# USER_IO.net
KiCad netlist of a schematic drawn in Altium Designer
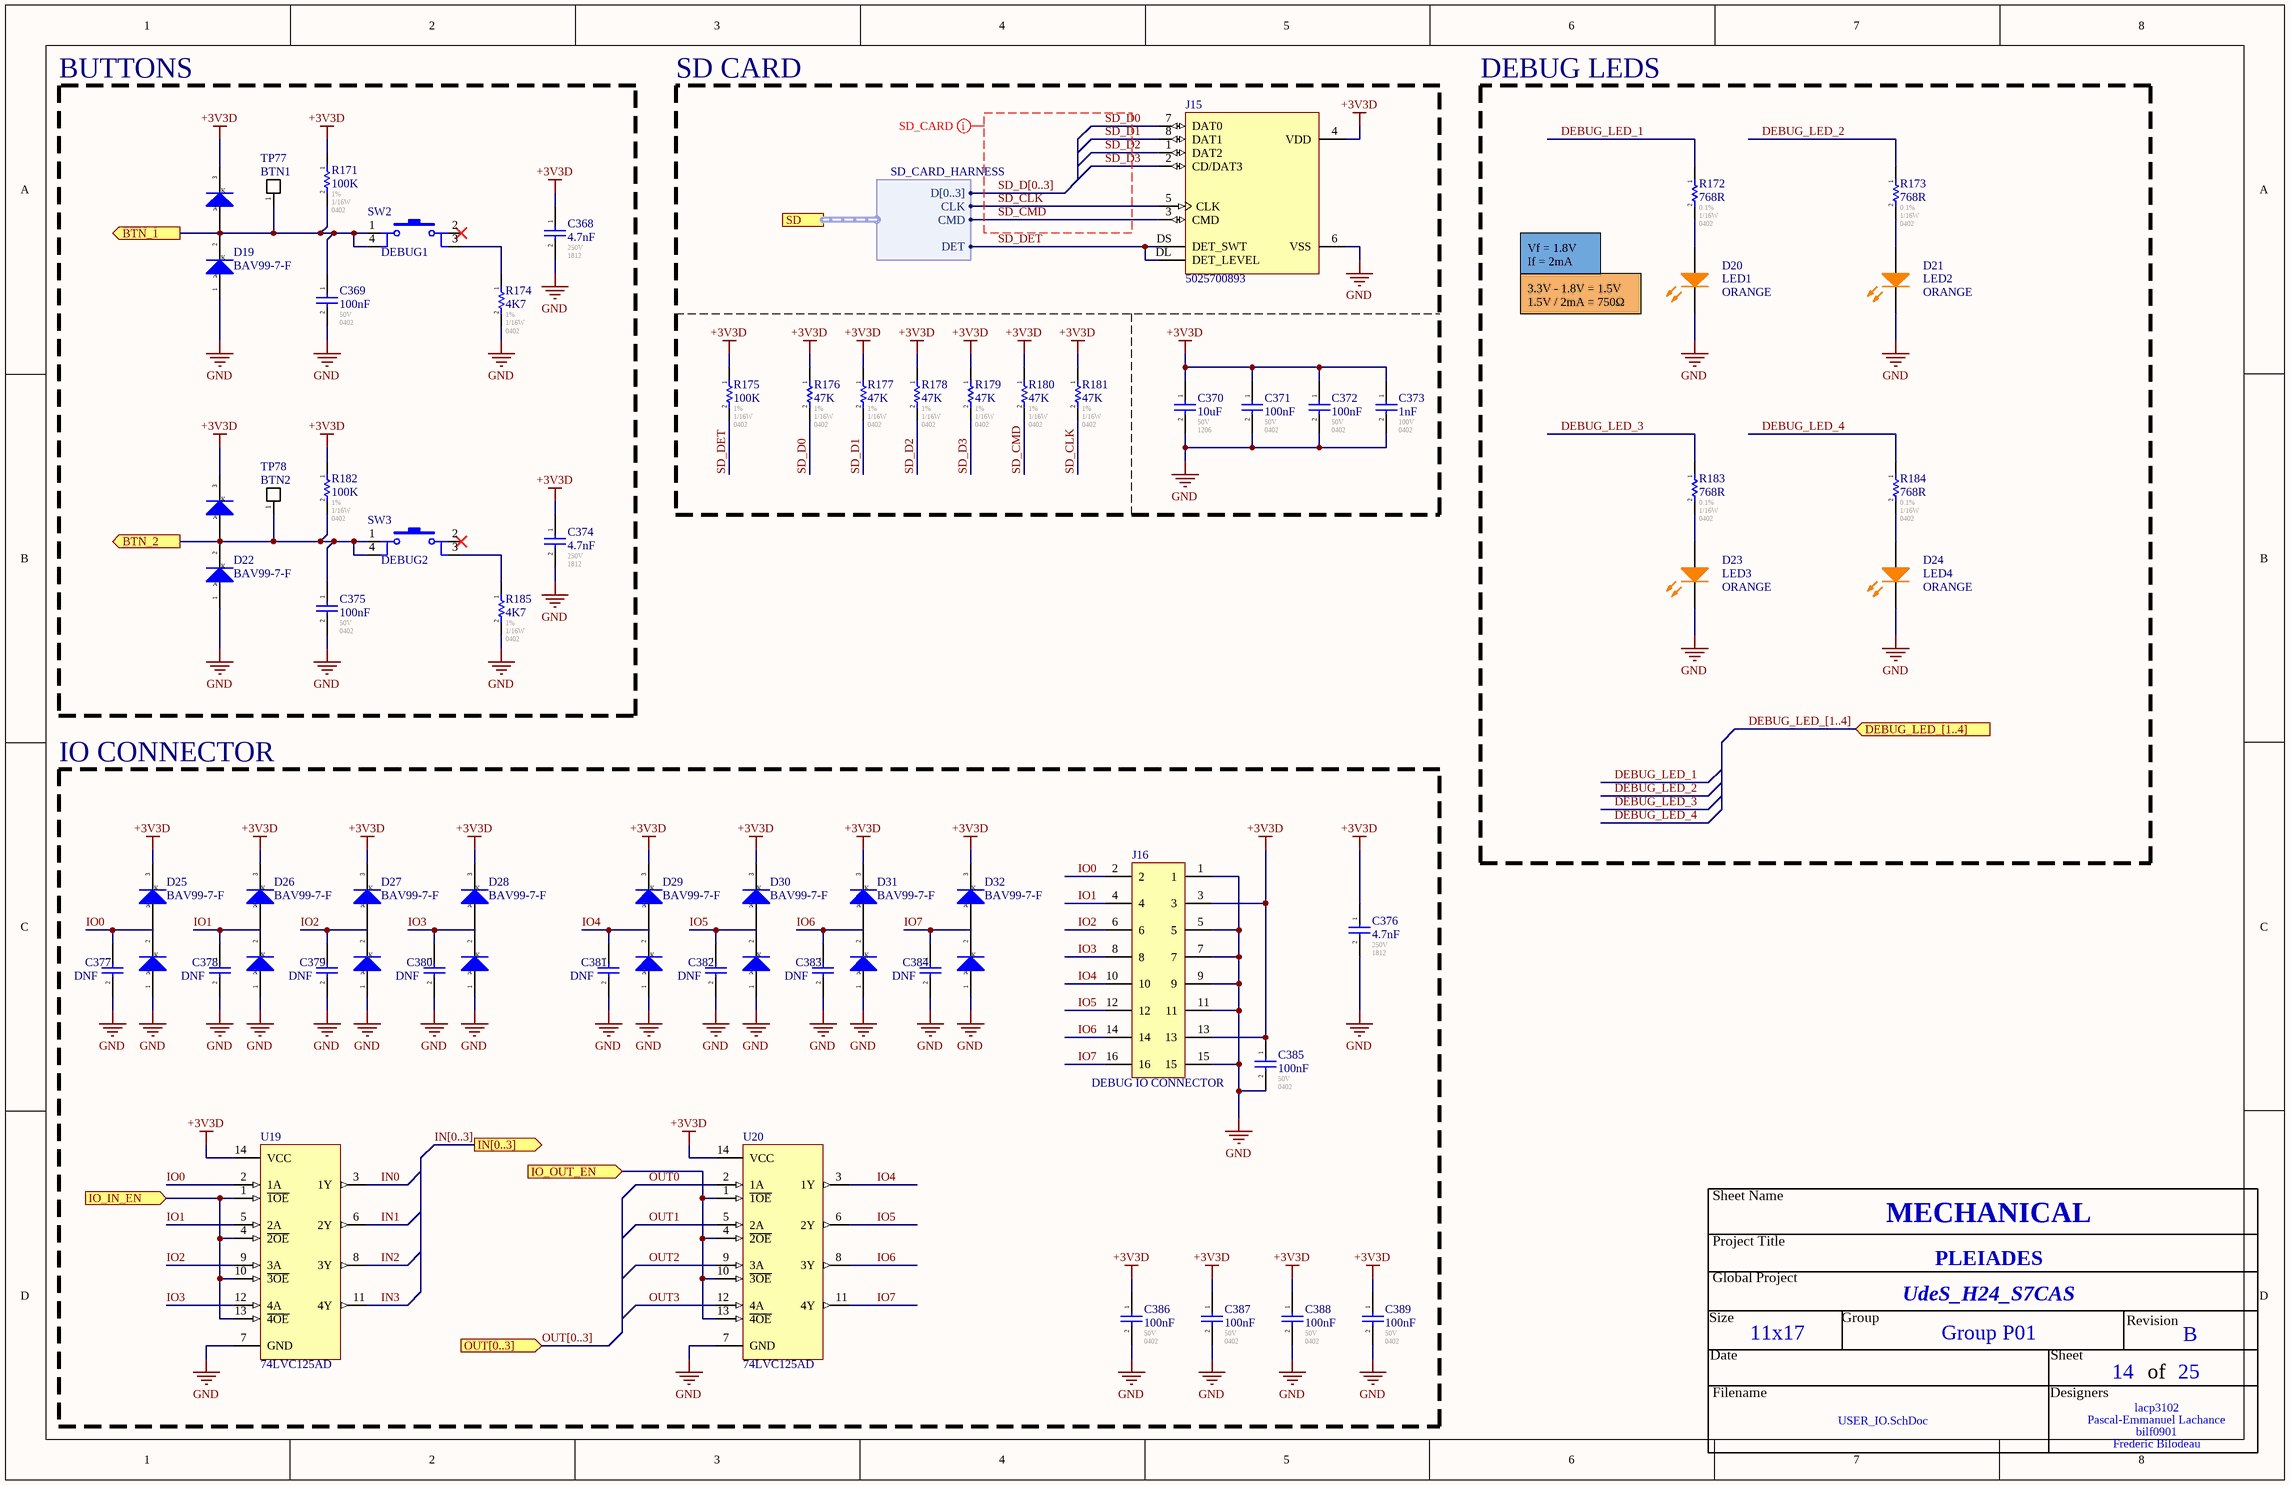
[diagram p0: USER_IO.SchDoc]

(export (version "E")
  (design (tool "Eeschema 10.0.6"))
  (components
    (comp (ref "C368")
      (value "4.7nF")
      (footprint "1812")
      (description "GA343DR7GD472KW01L\r\n0402 4.7nF 10% X7R 1812 250VAC Ceramic Capacitor")
      (fields
        (field (name "MFR") "Murata")
        (field (name "VOLTAGE - RATED") "250V")
        (field (name "TOLERANCE") "10%")
      )
      (libsource (lib "Symbols") (part "CAP_CER"))
    )
    (comp (ref "C369")
      (value "100nF")
      (footprint "0402")
      (description "GCM155R71H104KE02J\r\n0402 100nF 10% X7R Ceramic Capacitor")
      (fields
        (field (name "MFR") "Murata")
        (field (name "PART#") "GCM155R71H104KE02J")
        (field (name "VOLTAGE - RATED") "50V")
      )
      (libsource (lib "Symbols") (part "CAP_CER"))
    )
    (comp (ref "C370")
      (value "10uF")
      (footprint "1206")
      (description "GRT31CR61H106KE01L\r\n1206 10uF 10% X5R Ceramic Capacitor")
      (fields
        (field (name "MFR") "Murata")
        (field (name "VOLTAGE - RATED") "50V")
        (field (name "TOLERANCE") "10%")
      )
      (libsource (lib "Symbols") (part "CAP_CER"))
    )
    (comp (ref "C371")
      (value "100nF")
      (footprint "0402")
      (description "GCM155R71H104KE02J\r\n0402 100nF 10% X7R Ceramic Capacitor")
      (fields
        (field (name "MFR") "Murata")
        (field (name "PART#") "GCM155R71H104KE02J")
        (field (name "VOLTAGE - RATED") "50V")
      )
      (libsource (lib "Symbols") (part "CAP_CER"))
    )
    (comp (ref "C372")
      (value "100nF")
      (footprint "0402")
      (description "GCM155R71H104KE02J\r\n0402 100nF 10% X7R Ceramic Capacitor")
      (fields
        (field (name "MFR") "Murata")
        (field (name "PART#") "GCM155R71H104KE02J")
        (field (name "VOLTAGE - RATED") "50V")
      )
      (libsource (lib "Symbols") (part "CAP_CER"))
    )
    (comp (ref "C373")
      (value "1nF")
      (footprint "0402")
      (description "GCM155R72A102KA37D\r\n0402 1nF 10% X7R Ceramic Capacitor")
      (fields
        (field (name "MFR") "Murata")
        (field (name "PART#") "GCM155R72A102KA37D")
        (field (name "VOLTAGE - RATED") "100V")
      )
      (libsource (lib "Symbols") (part "CAP_CER"))
    )
    (comp (ref "C374")
      (value "4.7nF")
      (footprint "1812")
      (description "GA343DR7GD472KW01L\r\n0402 4.7nF 10% X7R 1812 250VAC Ceramic Capacitor")
      (fields
        (field (name "MFR") "Murata")
        (field (name "VOLTAGE - RATED") "250V")
        (field (name "TOLERANCE") "10%")
      )
      (libsource (lib "Symbols") (part "CAP_CER"))
    )
    (comp (ref "C375")
      (value "100nF")
      (footprint "0402")
      (description "GCM155R71H104KE02J\r\n0402 100nF 10% X7R Ceramic Capacitor")
      (fields
        (field (name "MFR") "Murata")
        (field (name "PART#") "GCM155R71H104KE02J")
        (field (name "VOLTAGE - RATED") "50V")
      )
      (libsource (lib "Symbols") (part "CAP_CER"))
    )
    (comp (ref "C376")
      (value "4.7nF")
      (footprint "1812")
      (description "GA343DR7GD472KW01L\r\n0402 4.7nF 10% X7R 1812 250VAC Ceramic Capacitor")
      (fields
        (field (name "MFR") "Murata")
        (field (name "VOLTAGE - RATED") "250V")
        (field (name "TOLERANCE") "10%")
      )
      (libsource (lib "Symbols") (part "CAP_CER"))
    )
    (comp (ref "C377") (value "DNF") (footprint "CAP_0402") (libsource (lib "Symbols") (part "CAP_CER")))
    (comp (ref "C378") (value "DNF") (footprint "CAP_0402") (libsource (lib "Symbols") (part "CAP_CER")))
    (comp (ref "C379") (value "DNF") (footprint "CAP_0402") (libsource (lib "Symbols") (part "CAP_CER")))
    (comp (ref "C380") (value "DNF") (footprint "CAP_0402") (libsource (lib "Symbols") (part "CAP_CER")))
    (comp (ref "C381") (value "DNF") (footprint "CAP_0402") (libsource (lib "Symbols") (part "CAP_CER")))
    (comp (ref "C382") (value "DNF") (footprint "CAP_0402") (libsource (lib "Symbols") (part "CAP_CER")))
    (comp (ref "C383") (value "DNF") (footprint "CAP_0402") (libsource (lib "Symbols") (part "CAP_CER")))
    (comp (ref "C384") (value "DNF") (footprint "CAP_0402") (libsource (lib "Symbols") (part "CAP_CER")))
    (comp (ref "C385")
      (value "100nF")
      (footprint "0402")
      (description "GCM155R71H104KE02J\r\n0402 100nF 10% X7R Ceramic Capacitor")
      (fields
        (field (name "MFR") "Murata")
        (field (name "PART#") "GCM155R71H104KE02J")
        (field (name "VOLTAGE - RATED") "50V")
      )
      (libsource (lib "Symbols") (part "CAP_CER"))
    )
    (comp (ref "C386")
      (value "100nF")
      (footprint "0402")
      (description "GCM155R71H104KE02J\r\n0402 100nF 10% X7R Ceramic Capacitor")
      (fields
        (field (name "MFR") "Murata")
        (field (name "PART#") "GCM155R71H104KE02J")
        (field (name "VOLTAGE - RATED") "50V")
      )
      (libsource (lib "Symbols") (part "CAP_CER"))
    )
    (comp (ref "C387")
      (value "100nF")
      (footprint "0402")
      (description "GCM155R71H104KE02J\r\n0402 100nF 10% X7R Ceramic Capacitor")
      (fields
        (field (name "MFR") "Murata")
        (field (name "PART#") "GCM155R71H104KE02J")
        (field (name "VOLTAGE - RATED") "50V")
      )
      (libsource (lib "Symbols") (part "CAP_CER"))
    )
    (comp (ref "C388")
      (value "100nF")
      (footprint "0402")
      (description "GCM155R71H104KE02J\r\n0402 100nF 10% X7R Ceramic Capacitor")
      (fields
        (field (name "MFR") "Murata")
        (field (name "PART#") "GCM155R71H104KE02J")
        (field (name "VOLTAGE - RATED") "50V")
      )
      (libsource (lib "Symbols") (part "CAP_CER"))
    )
    (comp (ref "C389")
      (value "100nF")
      (footprint "0402")
      (description "GCM155R71H104KE02J\r\n0402 100nF 10% X7R Ceramic Capacitor")
      (fields
        (field (name "MFR") "Murata")
        (field (name "PART#") "GCM155R71H104KE02J")
        (field (name "VOLTAGE - RATED") "50V")
      )
      (libsource (lib "Symbols") (part "CAP_CER"))
    )
    (comp (ref "D19")
      (value "BAV99-7-F")
      (footprint "SOT23-3")
      (description "Diode Array 1 Pair Series Connection 75 V 300mA (DC) Surface Mount TO-236-3, SC-59, SOT-23-3")
      (fields (field (name "MFR") "Diodes Incorporated"))
      (libsource (lib "Symbols") (part "DIODE_TVS_DUAL"))
    )
    (comp (ref "D20")
      (value "LED1")
      (footprint "LED_0603")
      (description "LED - 611nM ORANGE 2mA - 0603")
      (fields
        (field (name "VOLTAGE") "1.8V")
        (field (name "MFG") "ROHM Semiconductor")
        (field (name "ALTIUM_VALUE") "ORANGE")
        (field (name "CREATEDBY") "Jonathan Bouchard")
      )
      (libsource (lib "S7CAS_LIB2023") (part "LED_SML-311DTT86"))
    )
    (comp (ref "D21")
      (value "LED2")
      (footprint "LED_0603")
      (description "LED - 611nM ORANGE 2mA - 0603")
      (fields
        (field (name "VOLTAGE") "1.8V")
        (field (name "MFG") "ROHM Semiconductor")
        (field (name "ALTIUM_VALUE") "ORANGE")
        (field (name "CREATEDBY") "Jonathan Bouchard")
      )
      (libsource (lib "S7CAS_LIB2023") (part "LED_SML-311DTT86"))
    )
    (comp (ref "D22")
      (value "BAV99-7-F")
      (footprint "SOT23-3")
      (description "Diode Array 1 Pair Series Connection 75 V 300mA (DC) Surface Mount TO-236-3, SC-59, SOT-23-3")
      (fields (field (name "MFR") "Diodes Incorporated"))
      (libsource (lib "Symbols") (part "DIODE_TVS_DUAL"))
    )
    (comp (ref "D23")
      (value "LED3")
      (footprint "LED_0603")
      (description "LED - 611nM ORANGE 2mA - 0603")
      (fields
        (field (name "VOLTAGE") "1.8V")
        (field (name "MFG") "ROHM Semiconductor")
        (field (name "ALTIUM_VALUE") "ORANGE")
        (field (name "CREATEDBY") "Jonathan Bouchard")
      )
      (libsource (lib "S7CAS_LIB2023") (part "LED_SML-311DTT86"))
    )
    (comp (ref "D24")
      (value "LED4")
      (footprint "LED_0603")
      (description "LED - 611nM ORANGE 2mA - 0603")
      (fields
        (field (name "VOLTAGE") "1.8V")
        (field (name "MFG") "ROHM Semiconductor")
        (field (name "ALTIUM_VALUE") "ORANGE")
        (field (name "CREATEDBY") "Jonathan Bouchard")
      )
      (libsource (lib "S7CAS_LIB2023") (part "LED_SML-311DTT86"))
    )
    (comp (ref "D25")
      (value "BAV99-7-F")
      (footprint "SOT23-3")
      (description "Diode Array 1 Pair Series Connection 75 V 300mA (DC) Surface Mount TO-236-3, SC-59, SOT-23-3")
      (fields (field (name "MFR") "Diodes Incorporated"))
      (libsource (lib "Symbols") (part "DIODE_TVS_DUAL"))
    )
    (comp (ref "D26")
      (value "BAV99-7-F")
      (footprint "SOT23-3")
      (description "Diode Array 1 Pair Series Connection 75 V 300mA (DC) Surface Mount TO-236-3, SC-59, SOT-23-3")
      (fields (field (name "MFR") "Diodes Incorporated"))
      (libsource (lib "Symbols") (part "DIODE_TVS_DUAL"))
    )
    (comp (ref "D27")
      (value "BAV99-7-F")
      (footprint "SOT23-3")
      (description "Diode Array 1 Pair Series Connection 75 V 300mA (DC) Surface Mount TO-236-3, SC-59, SOT-23-3")
      (fields (field (name "MFR") "Diodes Incorporated"))
      (libsource (lib "Symbols") (part "DIODE_TVS_DUAL"))
    )
    (comp (ref "D28")
      (value "BAV99-7-F")
      (footprint "SOT23-3")
      (description "Diode Array 1 Pair Series Connection 75 V 300mA (DC) Surface Mount TO-236-3, SC-59, SOT-23-3")
      (fields (field (name "MFR") "Diodes Incorporated"))
      (libsource (lib "Symbols") (part "DIODE_TVS_DUAL"))
    )
    (comp (ref "D29")
      (value "BAV99-7-F")
      (footprint "SOT23-3")
      (description "Diode Array 1 Pair Series Connection 75 V 300mA (DC) Surface Mount TO-236-3, SC-59, SOT-23-3")
      (fields (field (name "MFR") "Diodes Incorporated"))
      (libsource (lib "Symbols") (part "DIODE_TVS_DUAL"))
    )
    (comp (ref "D30")
      (value "BAV99-7-F")
      (footprint "SOT23-3")
      (description "Diode Array 1 Pair Series Connection 75 V 300mA (DC) Surface Mount TO-236-3, SC-59, SOT-23-3")
      (fields (field (name "MFR") "Diodes Incorporated"))
      (libsource (lib "Symbols") (part "DIODE_TVS_DUAL"))
    )
    (comp (ref "D31")
      (value "BAV99-7-F")
      (footprint "SOT23-3")
      (description "Diode Array 1 Pair Series Connection 75 V 300mA (DC) Surface Mount TO-236-3, SC-59, SOT-23-3")
      (fields (field (name "MFR") "Diodes Incorporated"))
      (libsource (lib "Symbols") (part "DIODE_TVS_DUAL"))
    )
    (comp (ref "D32")
      (value "BAV99-7-F")
      (footprint "SOT23-3")
      (description "Diode Array 1 Pair Series Connection 75 V 300mA (DC) Surface Mount TO-236-3, SC-59, SOT-23-3")
      (fields (field (name "MFR") "Diodes Incorporated"))
      (libsource (lib "Symbols") (part "DIODE_TVS_DUAL"))
    )
    (comp (ref "J15")
      (value "5025700893")
      (footprint "MICROSD_5025700893")
      (description "10 (8 + 2) Position Card Connector Secure Digital - microSD™ Surface Mount, Right Angle Gold")
      (libsource (lib "Connectors") (part "MICROSD_10"))
    )
    (comp (ref "J16")
      (value "DEBUG IO CONNECTOR")
      (footprint "HEADER-16_100MIL")
      (libsource (lib "Connectors") (part "HEADER_16"))
    )
    (comp (ref "R171")
      (value "100K")
      (footprint "RES_0402")
      (fields
        (field (name "TOLERANCE") "1%")
        (field (name "POWER") "1/16W")
        (field (name "PACKAGE / CASE") "0402")
      )
      (libsource (lib "Symbols") (part "RESISTOR"))
    )
    (comp (ref "R172")
      (value "768R")
      (footprint "RES_0402")
      (fields
        (field (name "TOLERANCE") "0.1%")
        (field (name "POWER") "1/16W")
        (field (name "PACKAGE / CASE") "0402")
      )
      (libsource (lib "Symbols") (part "RESISTOR"))
    )
    (comp (ref "R173")
      (value "768R")
      (footprint "RES_0402")
      (fields
        (field (name "TOLERANCE") "0.1%")
        (field (name "POWER") "1/16W")
        (field (name "PACKAGE / CASE") "0402")
      )
      (libsource (lib "Symbols") (part "RESISTOR"))
    )
    (comp (ref "R174")
      (value "4K7")
      (footprint "RES_0402")
      (fields
        (field (name "TOLERANCE") "1%")
        (field (name "POWER") "1/16W")
        (field (name "PACKAGE / CASE") "0402")
      )
      (libsource (lib "Symbols") (part "RESISTOR"))
    )
    (comp (ref "R175")
      (value "100K")
      (footprint "RES_0402")
      (fields
        (field (name "TOLERANCE") "1%")
        (field (name "POWER") "1/16W")
        (field (name "PACKAGE / CASE") "0402")
      )
      (libsource (lib "Symbols") (part "RESISTOR"))
    )
    (comp (ref "R176")
      (value "47K")
      (footprint "RES_0402")
      (fields
        (field (name "TOLERANCE") "1%")
        (field (name "POWER") "1/16W")
        (field (name "PACKAGE / CASE") "0402")
      )
      (libsource (lib "Symbols") (part "RESISTOR"))
    )
    (comp (ref "R177")
      (value "47K")
      (footprint "RES_0402")
      (fields
        (field (name "TOLERANCE") "1%")
        (field (name "POWER") "1/16W")
        (field (name "PACKAGE / CASE") "0402")
      )
      (libsource (lib "Symbols") (part "RESISTOR"))
    )
    (comp (ref "R178")
      (value "47K")
      (footprint "RES_0402")
      (fields
        (field (name "TOLERANCE") "1%")
        (field (name "POWER") "1/16W")
        (field (name "PACKAGE / CASE") "0402")
      )
      (libsource (lib "Symbols") (part "RESISTOR"))
    )
    (comp (ref "R179")
      (value "47K")
      (footprint "RES_0402")
      (fields
        (field (name "TOLERANCE") "1%")
        (field (name "POWER") "1/16W")
        (field (name "PACKAGE / CASE") "0402")
      )
      (libsource (lib "Symbols") (part "RESISTOR"))
    )
    (comp (ref "R180")
      (value "47K")
      (footprint "RES_0402")
      (fields
        (field (name "TOLERANCE") "1%")
        (field (name "POWER") "1/16W")
        (field (name "PACKAGE / CASE") "0402")
      )
      (libsource (lib "Symbols") (part "RESISTOR"))
    )
    (comp (ref "R181")
      (value "47K")
      (footprint "RES_0402")
      (fields
        (field (name "TOLERANCE") "1%")
        (field (name "POWER") "1/16W")
        (field (name "PACKAGE / CASE") "0402")
      )
      (libsource (lib "Symbols") (part "RESISTOR"))
    )
    (comp (ref "R182")
      (value "100K")
      (footprint "RES_0402")
      (fields
        (field (name "TOLERANCE") "1%")
        (field (name "POWER") "1/16W")
        (field (name "PACKAGE / CASE") "0402")
      )
      (libsource (lib "Symbols") (part "RESISTOR"))
    )
    (comp (ref "R183")
      (value "768R")
      (footprint "RES_0402")
      (fields
        (field (name "TOLERANCE") "0.1%")
        (field (name "POWER") "1/16W")
        (field (name "PACKAGE / CASE") "0402")
      )
      (libsource (lib "Symbols") (part "RESISTOR"))
    )
    (comp (ref "R184")
      (value "768R")
      (footprint "RES_0402")
      (fields
        (field (name "TOLERANCE") "0.1%")
        (field (name "POWER") "1/16W")
        (field (name "PACKAGE / CASE") "0402")
      )
      (libsource (lib "Symbols") (part "RESISTOR"))
    )
    (comp (ref "R185")
      (value "4K7")
      (footprint "RES_0402")
      (fields
        (field (name "TOLERANCE") "1%")
        (field (name "POWER") "1/16W")
        (field (name "PACKAGE / CASE") "0402")
      )
      (libsource (lib "Symbols") (part "RESISTOR"))
    )
    (comp (ref "SW2")
      (value "DEBUG1")
      (footprint "SWI_TACT_B3SN-3012P")
      (description "SWI - TACT SPST-NO 0.05A 24V - 4-SMD")
      (fields
        (field (name "MFG") "Omron")
        (field (name "MFG PART NUMBER") "B3SN-3012P")
        (field (name "CREATEDBY") "Jonathan Bouchard")
      )
      (libsource (lib "S7CAS_LIB2023") (part "SWI_TACT_B3SN-3012P"))
    )
    (comp (ref "SW3")
      (value "DEBUG2")
      (footprint "SWI_TACT_B3SN-3012P")
      (description "SWI - TACT SPST-NO 0.05A 24V - 4-SMD")
      (fields
        (field (name "MFG") "Omron")
        (field (name "MFG PART NUMBER") "B3SN-3012P")
        (field (name "CREATEDBY") "Jonathan Bouchard")
      )
      (libsource (lib "S7CAS_LIB2023") (part "SWI_TACT_B3SN-3012P"))
    )
    (comp (ref "TP77")
      (value "BTN1")
      (footprint "TP_PAD")
      (description "Test Point")
      (libsource (lib "Symbols") (part "TESTPOINT_PAD"))
    )
    (comp (ref "TP78")
      (value "BTN2")
      (footprint "TP_PAD")
      (description "Test Point")
      (libsource (lib "Symbols") (part "TESTPOINT_PAD"))
    )
    (comp (ref "U19")
      (value "74LVC125AD")
      (footprint "SOIC-14_3.8MM")
      (description "Buffer, Non-Inverting 4 Element 1 Bit per Element 3-State Output 14-SO")
      (fields (field (name "MFR") "Nexperia"))
      (libsource (lib "Misc") (part "74LVC125AD,118"))
    )
    (comp (ref "U20")
      (value "74LVC125AD")
      (footprint "SOIC-14_3.8MM")
      (description "Buffer, Non-Inverting 4 Element 1 Bit per Element 3-State Output 14-SO")
      (fields (field (name "MFR") "Nexperia"))
      (libsource (lib "Misc") (part "74LVC125AD,118"))
    )
  )
  (nets
    (net (code "2") (name "+3V3D") (class "Default")
      (node (ref "C368") (pin "1") (pinfunction "1_1") (pintype "passive"))
      (node (ref "C370") (pin "1") (pinfunction "1_1") (pintype "passive"))
      (node (ref "C371") (pin "1") (pinfunction "1_1") (pintype "passive"))
      (node (ref "C372") (pin "1") (pinfunction "1_1") (pintype "passive"))
      (node (ref "C373") (pin "1") (pinfunction "1_1") (pintype "passive"))
      (node (ref "C374") (pin "1") (pinfunction "1_1") (pintype "passive"))
      (node (ref "C376") (pin "1") (pinfunction "1_1") (pintype "passive"))
      (node (ref "C385") (pin "1") (pinfunction "1_1") (pintype "passive"))
      (node (ref "C386") (pin "1") (pinfunction "1_1") (pintype "passive"))
      (node (ref "C387") (pin "1") (pinfunction "1_1") (pintype "passive"))
      (node (ref "C388") (pin "1") (pinfunction "1_1") (pintype "passive"))
      (node (ref "C389") (pin "1") (pinfunction "1_1") (pintype "passive"))
      (node (ref "D19") (pin "3") (pinfunction "K_3") (pintype "passive"))
      (node (ref "D22") (pin "3") (pinfunction "K_3") (pintype "passive"))
      (node (ref "D25") (pin "3") (pinfunction "K_3") (pintype "passive"))
      (node (ref "D26") (pin "3") (pinfunction "K_3") (pintype "passive"))
      (node (ref "D27") (pin "3") (pinfunction "K_3") (pintype "passive"))
      (node (ref "D28") (pin "3") (pinfunction "K_3") (pintype "passive"))
      (node (ref "D29") (pin "3") (pinfunction "K_3") (pintype "passive"))
      (node (ref "D30") (pin "3") (pinfunction "K_3") (pintype "passive"))
      (node (ref "D31") (pin "3") (pinfunction "K_3") (pintype "passive"))
      (node (ref "D32") (pin "3") (pinfunction "K_3") (pintype "passive"))
      (node (ref "J15") (pin "4") (pinfunction "VDD_4") (pintype "power_in"))
      (node (ref "J16") (pin "13") (pinfunction "13_13") (pintype "passive"))
      (node (ref "J16") (pin "3") (pinfunction "3_3") (pintype "passive"))
      (node (ref "R171") (pin "1") (pinfunction "1_1") (pintype "passive"))
      (node (ref "R175") (pin "1") (pinfunction "1_1") (pintype "passive"))
      (node (ref "R176") (pin "1") (pinfunction "1_1") (pintype "passive"))
      (node (ref "R177") (pin "1") (pinfunction "1_1") (pintype "passive"))
      (node (ref "R178") (pin "1") (pinfunction "1_1") (pintype "passive"))
      (node (ref "R179") (pin "1") (pinfunction "1_1") (pintype "passive"))
      (node (ref "R180") (pin "1") (pinfunction "1_1") (pintype "passive"))
      (node (ref "R181") (pin "1") (pinfunction "1_1") (pintype "passive"))
      (node (ref "R182") (pin "1") (pinfunction "1_1") (pintype "passive"))
      (node (ref "U19") (pin "14") (pinfunction "VCC_14") (pintype "power_in"))
      (node (ref "U20") (pin "14") (pinfunction "VCC_14") (pintype "power_in"))
    )
    (net (code "3") (name "/BTN_1") (class "Default")
      (node (ref "C369") (pin "1") (pinfunction "1_1") (pintype "passive"))
      (node (ref "D19") (pin "2") (pinfunction "K_2") (pintype "passive"))
      (node (ref "R171") (pin "2") (pinfunction "2_2") (pintype "passive"))
      (node (ref "SW2") (pin "1") (pinfunction "1_1") (pintype "passive"))
      (node (ref "SW2") (pin "4") (pinfunction "4_4") (pintype "passive"))
      (node (ref "TP77") (pin "1") (pinfunction "A_1") (pintype "passive"))
    )
    (net (code "4") (name "/BTN_2") (class "Default")
      (node (ref "C375") (pin "1") (pinfunction "1_1") (pintype "passive"))
      (node (ref "D22") (pin "2") (pinfunction "K_2") (pintype "passive"))
      (node (ref "R182") (pin "2") (pinfunction "2_2") (pintype "passive"))
      (node (ref "SW3") (pin "1") (pinfunction "1_1") (pintype "passive"))
      (node (ref "SW3") (pin "4") (pinfunction "4_4") (pintype "passive"))
      (node (ref "TP78") (pin "1") (pinfunction "A_1") (pintype "passive"))
    )
    (net (code "5") (name "/DEBUG_LED_1") (class "Default")
      (node (ref "R172") (pin "1") (pinfunction "1_1") (pintype "passive"))
    )
    (net (code "6") (name "/DEBUG_LED_2") (class "Default")
      (node (ref "R173") (pin "1") (pinfunction "1_1") (pintype "passive"))
    )
    (net (code "7") (name "/DEBUG_LED_3") (class "Default")
      (node (ref "R183") (pin "1") (pinfunction "1_1") (pintype "passive"))
    )
    (net (code "8") (name "/DEBUG_LED_4") (class "Default")
      (node (ref "R184") (pin "1") (pinfunction "1_1") (pintype "passive"))
    )
    (net (code "10") (name "/IN0") (class "Default")
      (node (ref "U19") (pin "3") (pinfunction "1Y_3") (pintype "output"))
    )
    (net (code "11") (name "/IN1") (class "Default")
      (node (ref "U19") (pin "6") (pinfunction "2Y_6") (pintype "output"))
    )
    (net (code "12") (name "/IN2") (class "Default")
      (node (ref "U19") (pin "8") (pinfunction "3Y_8") (pintype "output"))
    )
    (net (code "13") (name "/IN3") (class "Default")
      (node (ref "U19") (pin "11") (pinfunction "4Y_11") (pintype "output"))
    )
    (net (code "15") (name "/IO0") (class "Default")
      (node (ref "C377") (pin "1") (pinfunction "1_1") (pintype "passive"))
      (node (ref "D25") (pin "2") (pinfunction "K_2") (pintype "passive"))
      (node (ref "J16") (pin "2") (pinfunction "2_2") (pintype "passive"))
      (node (ref "U19") (pin "2") (pinfunction "1A_2") (pintype "input"))
    )
    (net (code "16") (name "/IO1") (class "Default")
      (node (ref "C378") (pin "1") (pinfunction "1_1") (pintype "passive"))
      (node (ref "D26") (pin "2") (pinfunction "K_2") (pintype "passive"))
      (node (ref "J16") (pin "4") (pinfunction "4_4") (pintype "passive"))
      (node (ref "U19") (pin "5") (pinfunction "2A_5") (pintype "input"))
    )
    (net (code "17") (name "/IO2") (class "Default")
      (node (ref "C379") (pin "1") (pinfunction "1_1") (pintype "passive"))
      (node (ref "D27") (pin "2") (pinfunction "K_2") (pintype "passive"))
      (node (ref "J16") (pin "6") (pinfunction "6_6") (pintype "passive"))
      (node (ref "U19") (pin "9") (pinfunction "3A_9") (pintype "input"))
    )
    (net (code "18") (name "/IO3") (class "Default")
      (node (ref "C380") (pin "1") (pinfunction "1_1") (pintype "passive"))
      (node (ref "D28") (pin "2") (pinfunction "K_2") (pintype "passive"))
      (node (ref "J16") (pin "8") (pinfunction "8_8") (pintype "passive"))
      (node (ref "U19") (pin "12") (pinfunction "4A_12") (pintype "input"))
    )
    (net (code "19") (name "/IO4") (class "Default")
      (node (ref "C381") (pin "1") (pinfunction "1_1") (pintype "passive"))
      (node (ref "D29") (pin "2") (pinfunction "K_2") (pintype "passive"))
      (node (ref "J16") (pin "10") (pinfunction "10_10") (pintype "passive"))
      (node (ref "U20") (pin "3") (pinfunction "1Y_3") (pintype "output"))
    )
    (net (code "20") (name "/IO5") (class "Default")
      (node (ref "C382") (pin "1") (pinfunction "1_1") (pintype "passive"))
      (node (ref "D30") (pin "2") (pinfunction "K_2") (pintype "passive"))
      (node (ref "J16") (pin "12") (pinfunction "12_12") (pintype "passive"))
      (node (ref "U20") (pin "6") (pinfunction "2Y_6") (pintype "output"))
    )
    (net (code "21") (name "/IO6") (class "Default")
      (node (ref "C383") (pin "1") (pinfunction "1_1") (pintype "passive"))
      (node (ref "D31") (pin "2") (pinfunction "K_2") (pintype "passive"))
      (node (ref "J16") (pin "14") (pinfunction "14_14") (pintype "passive"))
      (node (ref "U20") (pin "8") (pinfunction "3Y_8") (pintype "output"))
    )
    (net (code "22") (name "/IO7") (class "Default")
      (node (ref "C384") (pin "1") (pinfunction "1_1") (pintype "passive"))
      (node (ref "D32") (pin "2") (pinfunction "K_2") (pintype "passive"))
      (node (ref "J16") (pin "16") (pinfunction "16_16") (pintype "passive"))
      (node (ref "U20") (pin "11") (pinfunction "4Y_11") (pintype "output"))
    )
    (net (code "23") (name "/IO_IN_EN") (class "Default")
      (node (ref "U19") (pin "1") (pinfunction "1OE_1") (pintype "input"))
      (node (ref "U19") (pin "10") (pinfunction "3OE_10") (pintype "input"))
      (node (ref "U19") (pin "13") (pinfunction "4OE_13") (pintype "input"))
      (node (ref "U19") (pin "4") (pinfunction "2OE_4") (pintype "input"))
    )
    (net (code "24") (name "/IO_OUT_EN") (class "Default")
      (node (ref "U20") (pin "1") (pinfunction "1OE_1") (pintype "input"))
      (node (ref "U20") (pin "10") (pinfunction "3OE_10") (pintype "input"))
      (node (ref "U20") (pin "13") (pinfunction "4OE_13") (pintype "input"))
      (node (ref "U20") (pin "4") (pinfunction "2OE_4") (pintype "input"))
    )
    (net (code "25") (name "/OUT0") (class "Default")
      (node (ref "U20") (pin "2") (pinfunction "1A_2") (pintype "input"))
    )
    (net (code "26") (name "/OUT1") (class "Default")
      (node (ref "U20") (pin "5") (pinfunction "2A_5") (pintype "input"))
    )
    (net (code "27") (name "/OUT2") (class "Default")
      (node (ref "U20") (pin "9") (pinfunction "3A_9") (pintype "input"))
    )
    (net (code "28") (name "/OUT3") (class "Default")
      (node (ref "U20") (pin "12") (pinfunction "4A_12") (pintype "input"))
    )
    (net (code "30") (name "/SD_CLK") (class "Default")
      (node (ref "J15") (pin "5") (pinfunction "CLK_5") (pintype "input"))
      (node (ref "R181") (pin "2") (pinfunction "2_2") (pintype "passive"))
    )
    (net (code "31") (name "/SD_CMD") (class "Default")
      (node (ref "J15") (pin "3") (pinfunction "CMD_3") (pintype "bidirectional"))
      (node (ref "R180") (pin "2") (pinfunction "2_2") (pintype "passive"))
    )
    (net (code "32") (name "/SD_D0") (class "Default")
      (node (ref "J15") (pin "7") (pinfunction "DAT0_7") (pintype "bidirectional"))
      (node (ref "R176") (pin "2") (pinfunction "2_2") (pintype "passive"))
    )
    (net (code "33") (name "/SD_D1") (class "Default")
      (node (ref "J15") (pin "8") (pinfunction "DAT1_8") (pintype "bidirectional"))
      (node (ref "R177") (pin "2") (pinfunction "2_2") (pintype "passive"))
    )
    (net (code "34") (name "/SD_D2") (class "Default")
      (node (ref "J15") (pin "1") (pinfunction "DAT2_1") (pintype "bidirectional"))
      (node (ref "R178") (pin "2") (pinfunction "2_2") (pintype "passive"))
    )
    (net (code "35") (name "/SD_D3") (class "Default")
      (node (ref "J15") (pin "2") (pinfunction "CD/DAT3_2") (pintype "bidirectional"))
      (node (ref "R179") (pin "2") (pinfunction "2_2") (pintype "passive"))
    )
    (net (code "36") (name "/SD_DET") (class "Default")
      (node (ref "J15") (pin "DL") (pinfunction "DET_LEVEL_DL") (pintype "passive"))
      (node (ref "J15") (pin "DS") (pinfunction "DET_SWT_DS") (pintype "passive"))
      (node (ref "R175") (pin "2") (pinfunction "2_2") (pintype "passive"))
    )
    (net (code "39") (name "GND") (class "Default")
      (node (ref "C368") (pin "2") (pinfunction "2_2") (pintype "passive"))
      (node (ref "C369") (pin "2") (pinfunction "2_2") (pintype "passive"))
      (node (ref "C370") (pin "2") (pinfunction "2_2") (pintype "passive"))
      (node (ref "C371") (pin "2") (pinfunction "2_2") (pintype "passive"))
      (node (ref "C372") (pin "2") (pinfunction "2_2") (pintype "passive"))
      (node (ref "C373") (pin "2") (pinfunction "2_2") (pintype "passive"))
      (node (ref "C374") (pin "2") (pinfunction "2_2") (pintype "passive"))
      (node (ref "C375") (pin "2") (pinfunction "2_2") (pintype "passive"))
      (node (ref "C376") (pin "2") (pinfunction "2_2") (pintype "passive"))
      (node (ref "C377") (pin "2") (pinfunction "2_2") (pintype "passive"))
      (node (ref "C378") (pin "2") (pinfunction "2_2") (pintype "passive"))
      (node (ref "C379") (pin "2") (pinfunction "2_2") (pintype "passive"))
      (node (ref "C380") (pin "2") (pinfunction "2_2") (pintype "passive"))
      (node (ref "C381") (pin "2") (pinfunction "2_2") (pintype "passive"))
      (node (ref "C382") (pin "2") (pinfunction "2_2") (pintype "passive"))
      (node (ref "C383") (pin "2") (pinfunction "2_2") (pintype "passive"))
      (node (ref "C384") (pin "2") (pinfunction "2_2") (pintype "passive"))
      (node (ref "C385") (pin "2") (pinfunction "2_2") (pintype "passive"))
      (node (ref "C386") (pin "2") (pinfunction "2_2") (pintype "passive"))
      (node (ref "C387") (pin "2") (pinfunction "2_2") (pintype "passive"))
      (node (ref "C388") (pin "2") (pinfunction "2_2") (pintype "passive"))
      (node (ref "C389") (pin "2") (pinfunction "2_2") (pintype "passive"))
      (node (ref "D19") (pin "1") (pinfunction "A_1") (pintype "passive"))
      (node (ref "D20") (pin "2") (pinfunction "K_2") (pintype "passive"))
      (node (ref "D21") (pin "2") (pinfunction "K_2") (pintype "passive"))
      (node (ref "D22") (pin "1") (pinfunction "A_1") (pintype "passive"))
      (node (ref "D23") (pin "2") (pinfunction "K_2") (pintype "passive"))
      (node (ref "D24") (pin "2") (pinfunction "K_2") (pintype "passive"))
      (node (ref "D25") (pin "1") (pinfunction "A_1") (pintype "passive"))
      (node (ref "D26") (pin "1") (pinfunction "A_1") (pintype "passive"))
      (node (ref "D27") (pin "1") (pinfunction "A_1") (pintype "passive"))
      (node (ref "D28") (pin "1") (pinfunction "A_1") (pintype "passive"))
      (node (ref "D29") (pin "1") (pinfunction "A_1") (pintype "passive"))
      (node (ref "D30") (pin "1") (pinfunction "A_1") (pintype "passive"))
      (node (ref "D31") (pin "1") (pinfunction "A_1") (pintype "passive"))
      (node (ref "D32") (pin "1") (pinfunction "A_1") (pintype "passive"))
      (node (ref "J15") (pin "6") (pinfunction "VSS_6") (pintype "power_in"))
      (node (ref "J16") (pin "1") (pinfunction "1_1") (pintype "passive"))
      (node (ref "J16") (pin "11") (pinfunction "11_11") (pintype "passive"))
      (node (ref "J16") (pin "15") (pinfunction "15_15") (pintype "passive"))
      (node (ref "J16") (pin "5") (pinfunction "5_5") (pintype "passive"))
      (node (ref "J16") (pin "7") (pinfunction "7_7") (pintype "passive"))
      (node (ref "J16") (pin "9") (pinfunction "9_9") (pintype "passive"))
      (node (ref "R174") (pin "2") (pinfunction "2_2") (pintype "passive"))
      (node (ref "R185") (pin "2") (pinfunction "2_2") (pintype "passive"))
      (node (ref "U19") (pin "7") (pinfunction "GND_7") (pintype "power_in"))
      (node (ref "U20") (pin "7") (pinfunction "GND_7") (pintype "power_in"))
    )
    (net (code "40") (name "Net-(D20-A)") (class "Default")
      (node (ref "D20") (pin "1") (pinfunction "A_1") (pintype "passive"))
      (node (ref "R172") (pin "2") (pinfunction "2_2") (pintype "passive"))
    )
    (net (code "41") (name "Net-(D21-A)") (class "Default")
      (node (ref "D21") (pin "1") (pinfunction "A_1") (pintype "passive"))
      (node (ref "R173") (pin "2") (pinfunction "2_2") (pintype "passive"))
    )
    (net (code "42") (name "Net-(D23-A)") (class "Default")
      (node (ref "D23") (pin "1") (pinfunction "A_1") (pintype "passive"))
      (node (ref "R183") (pin "2") (pinfunction "2_2") (pintype "passive"))
    )
    (net (code "43") (name "Net-(D24-A)") (class "Default")
      (node (ref "D24") (pin "1") (pinfunction "A_1") (pintype "passive"))
      (node (ref "R184") (pin "2") (pinfunction "2_2") (pintype "passive"))
    )
    (net (code "44") (name "Net-(R174-Pad1)") (class "Default")
      (node (ref "R174") (pin "1") (pinfunction "1_1") (pintype "passive"))
      (node (ref "SW2") (pin "3") (pinfunction "3_3") (pintype "passive"))
    )
    (net (code "45") (name "Net-(R185-Pad1)") (class "Default")
      (node (ref "R185") (pin "1") (pinfunction "1_1") (pintype "passive"))
      (node (ref "SW3") (pin "3") (pinfunction "3_3") (pintype "passive"))
    )
    (net (code "46") (name "unconnected-(SW2-Pad2)") (class "Default")
      (node (ref "SW2") (pin "2") (pinfunction "2_2") (pintype "passive+no_connect"))
    )
    (net (code "47") (name "unconnected-(SW3-Pad2)") (class "Default")
      (node (ref "SW3") (pin "2") (pinfunction "2_2") (pintype "passive+no_connect"))
    )
  )
)
